# RTU_LMG_Battery_Charger.net
KiCad netlist of a schematic drawn in Altium Designer
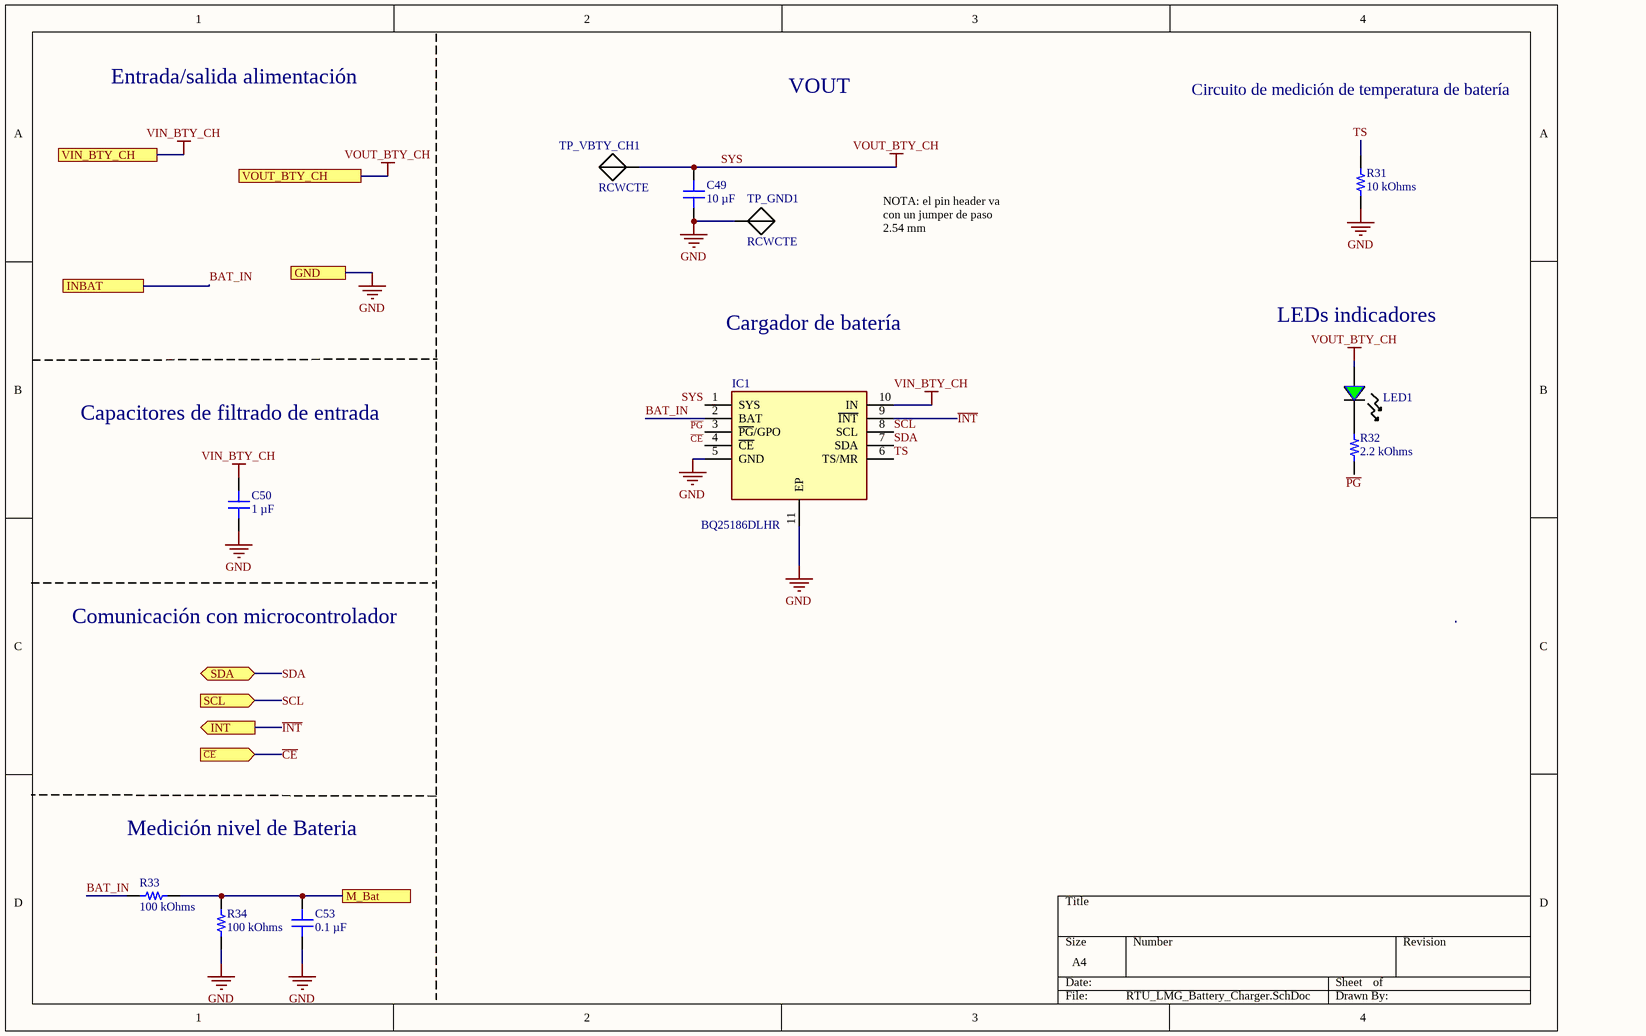
[diagram p0: RTU_LMG_Battery_Charger.SchDoc]

(export (version "E")
  (design (tool "Eeschema 10.0.6"))
  (components
    (comp (ref "C49")
      (value "10 µF")
      (footprint "CAP 0805_2012")
      (description "CAP CER 10UF 16V X5R 0805")
      (fields
        (field (name "PART NUMBER") "CL21A106KOQNNNE")
        (field (name "MANUFACTURER") "Samsung Electro-Mechanics")
      )
      (libsource (lib "Celestial Altium Library - altium_library") (part "Capacitor"))
    )
    (comp (ref "C50")
      (value "1 µF")
      (footprint "MURATA GRM155 0402_1005")
      (description "CAP CER 1UF 35V X5R 0402")
      (fields
        (field (name "PART NUMBER") "GRM155R6YA105KE11D")
        (field (name "MANUFACTURER") "Murata Electronics")
      )
      (libsource (lib "Celestial Altium Library - altium_library") (part "Capacitor"))
    )
    (comp (ref "C53")
      (value "0.1 µF")
      (footprint "CAP 0402_1005")
      (description "CAP CER 0.1UF 50V X5R 0402")
      (fields
        (field (name "PART NUMBER") "CGA2B3X5R1H104M050BB")
        (field (name "CAPACITANCE") "0.1 µF")
        (field (name "MANUFACTURER") "TDK Corporation")
      )
      (libsource (lib "Celestial Altium Library - altium_library") (part "Capacitor"))
    )
    (comp (ref "IC1")
      (value "BQ25186DLHR")
      (footprint "SON40P220X200X80-11N")
      (fields (field (name "MOUSER PART NUMBER") "595-BQ25186DLHR"))
      (libsource (lib "BQ25186DLHR") (part "BQ25186DLHR"))
    )
    (comp (ref "LED1")
      (value "LTST-C170GKT")
      (footprint "0805 SMD - LED")
      (description "LED verde SMD (0805)")
      (fields (field (name "COPYRIGHT") "Copyright (C) 2023 Ultra Librarian. All rights reserved."))
      (libsource (lib "DIN_DC_Base_Board_components_SCH_footprints") (part "LTST-C170GKT"))
    )
    (comp (ref "R31")
      (value "10 kOhms")
      (footprint "PCB - RESISTOR - CHIP - RES 0603_1608:RES 0603_1608")
      (description "RES 10K OHM 1% 1/10W 0603")
      (fields (field (name "PART NUMBER") "RC0603FR-0710KL") (field (name "MANUFACTURER") "Yageo"))
      (libsource (lib "Celestial Altium Library - altium_library") (part "Resistor"))
    )
    (comp (ref "R32")
      (value "2.2 kOhms")
      (footprint "RES 0402_1005")
      (description "RES SMD 2.2K OHM 1% 1/10W 0402")
      (fields
        (field (name "PART NUMBER") "ERJ-2RKF2201X")
        (field (name "MANUFACTURER") "Panasonic Electronic Components")
      )
      (libsource (lib "Celestial Altium Library - altium_library") (part "Resistor"))
    )
    (comp (ref "R33")
      (value "100 kOhms")
      (footprint "PCB - RESISTOR - CHIP - RES 0402_1005:RES 0402_1005")
      (description "RES SMD 100K OHM 1% 1/16W 0402")
      (fields (field (name "PART NUMBER") "CRCW0402100KFKED") (field (name "MANUFACTURER") "Vishay Dale"))
      (libsource (lib "Celestial Altium Library - altium_library") (part "Resistor"))
    )
    (comp (ref "R34")
      (value "100 kOhms")
      (footprint "PCB - RESISTOR - CHIP - RES 0402_1005:RES 0402_1005")
      (description "RES SMD 100K OHM 1% 1/16W 0402")
      (fields (field (name "PART NUMBER") "CRCW0402100KFKED") (field (name "MANUFACTURER") "Vishay Dale"))
      (libsource (lib "Celestial Altium Library - altium_library") (part "Resistor"))
    )
    (comp (ref "TP_GND1")
      (value "RCWCTE")
      (footprint "RCWCTE")
      (description "- PC Test Point - - Plating Surface Mount Mounting Type")
      (fields (field (name "MF") "KOA Speer") (field (name "DIGI-KEY_PART_NUMBER") "2019-RCWCTETR-ND"))
      (libsource (lib "DIN_DC_Base_Board_components") (part "RCWCTE"))
    )
    (comp (ref "TP_VBTY_CH1")
      (value "RCWCTE")
      (footprint "RCWCTE")
      (description "- PC Test Point - - Plating Surface Mount Mounting Type")
      (fields (field (name "MF") "KOA Speer") (field (name "DIGI-KEY_PART_NUMBER") "2019-RCWCTETR-ND"))
      (libsource (lib "DIN_DC_Base_Board_components") (part "RCWCTE"))
    )
  )
  (nets
    (net (code "1") (name "/BAT_IN") (class "Default")
      (node (ref "IC1") (pin "2") (pinfunction "BAT_2") (pintype "passive"))
      (node (ref "R33") (pin "1") (pinfunction "1_1") (pintype "passive"))
    )
    (net (code "2") (name "/M_Bat") (class "Default")
      (node (ref "C53") (pin "2") (pinfunction "2_2") (pintype "passive"))
      (node (ref "R33") (pin "2") (pinfunction "2_2") (pintype "passive"))
      (node (ref "R34") (pin "1") (pinfunction "1_1") (pintype "passive"))
    )
    (net (code "3") (name "/SCL") (class "Default")
      (node (ref "IC1") (pin "8") (pinfunction "SCL_8") (pintype "passive"))
    )
    (net (code "4") (name "/SDA") (class "Default")
      (node (ref "IC1") (pin "7") (pinfunction "SDA_7") (pintype "passive"))
    )
    (net (code "5") (name "/TS") (class "Default")
      (node (ref "IC1") (pin "6") (pinfunction "TS/MR_6") (pintype "passive"))
      (node (ref "R31") (pin "2") (pinfunction "2_2") (pintype "passive"))
    )
    (net (code "6") (name "/~{CE}") (class "Default")
      (node (ref "IC1") (pin "4") (pinfunction "~{CE}_4") (pintype "passive"))
    )
    (net (code "7") (name "/~{INT}") (class "Default")
      (node (ref "IC1") (pin "9") (pinfunction "~{INT}_9") (pintype "passive"))
    )
    (net (code "8") (name "/~{PG}") (class "Default")
      (node (ref "IC1") (pin "3") (pinfunction "~{PG}/GPO_3") (pintype "passive"))
      (node (ref "R32") (pin "1") (pinfunction "1_1") (pintype "passive"))
    )
    (net (code "9") (name "GND") (class "Default")
      (node (ref "C49") (pin "2") (pinfunction "2_2") (pintype "passive"))
      (node (ref "C50") (pin "1") (pinfunction "1_1") (pintype "passive"))
      (node (ref "C53") (pin "1") (pinfunction "1_1") (pintype "passive"))
      (node (ref "IC1") (pin "11") (pinfunction "EP_11") (pintype "passive"))
      (node (ref "IC1") (pin "5") (pinfunction "GND_5") (pintype "passive"))
      (node (ref "R31") (pin "1") (pinfunction "1_1") (pintype "passive"))
      (node (ref "R34") (pin "2") (pinfunction "2_2") (pintype "passive"))
      (node (ref "TP_GND1") (pin "1") (pinfunction "TP_1") (pintype "passive"))
    )
    (net (code "10") (name "Net-(LED1-CATHODE)") (class "Default")
      (node (ref "LED1") (pin "K") (pinfunction "CATHODE_K") (pintype "passive"))
      (node (ref "R32") (pin "2") (pinfunction "2_2") (pintype "passive"))
    )
    (net (code "11") (name "VIN_BTY_CH") (class "Default")
      (node (ref "C50") (pin "2") (pinfunction "2_2") (pintype "passive"))
      (node (ref "IC1") (pin "10") (pinfunction "IN_10") (pintype "passive"))
    )
    (net (code "12") (name "VOUT_BTY_CH") (class "Default")
      (node (ref "C49") (pin "1") (pinfunction "1_1") (pintype "passive"))
      (node (ref "IC1") (pin "1") (pinfunction "SYS_1") (pintype "passive"))
      (node (ref "LED1") (pin "A") (pinfunction "ANODE_A") (pintype "passive"))
      (node (ref "TP_VBTY_CH1") (pin "1") (pinfunction "TP_1") (pintype "passive"))
    )
  )
)
